# Audio_Alarm_Monitoring_Pi_Hat.net
KiCad netlist of a schematic drawn in EAGLE
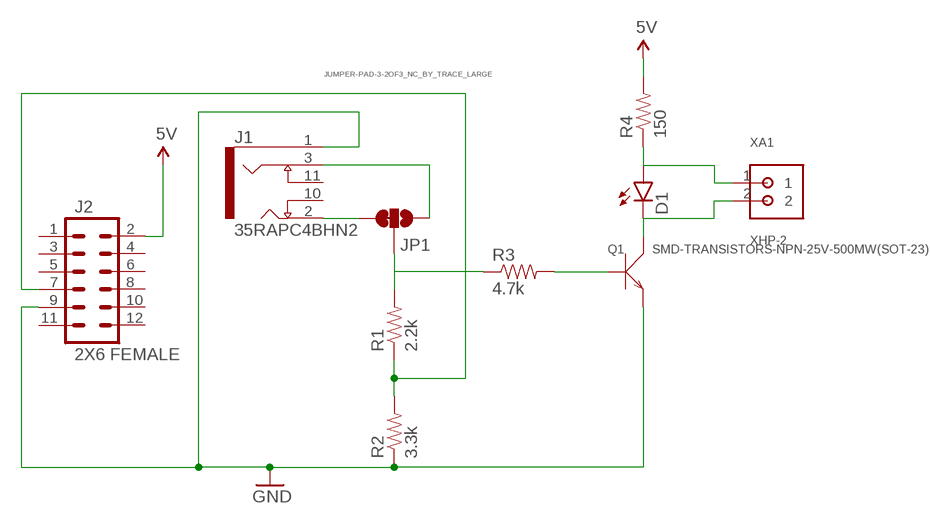
[diagram p0: schematic, sheet 1]

(export (version "E")
  (design (tool "Eeschema 10.0.6"))
  (components
    (comp (ref "D1")
      (value "LED1206")
      (footprint "eagle-import:LED-1206")
      (libsource (lib "eagle-import") (part "LED1206"))
    )
    (comp (ref "J1")
      (value "35RAPC4BHN2")
      (footprint "eagle-import:SWITCHCRAFT_35RAPC4BHN2")
      (fields (field (name "MF") "Switchcraft"))
      (libsource (lib "eagle-import") (part "35RAPC4BHN2"))
    )
    (comp (ref "J2")
      (value "2X6 FEMALE")
      (footprint "eagle-import:2X6")
      (libsource (lib "eagle-import") (part "M06X2PTH_FEMALE"))
    )
    (comp (ref "JP1")
      (value "JUMPER-PAD-3-2OF3_NC_BY_TRACE_LARGE")
      (footprint "eagle-import:PAD-JUMPER-3-2OF3_NC_BY_TRACE_YES_SILK_LARGE")
      (libsource (lib "eagle-import") (part "JUMPER-PAD-3-2OF3_NC_BY_TRACE_LARGE"))
    )
    (comp (ref "Q1")
      (value "SMD-TRANSISTORS-NPN-25V-500MW(SOT-23)")
      (footprint "eagle-import:SOT-23")
      (fields (field (name "MF") "Recom Power") (field (name "MP") "S8050"))
      (libsource (lib "eagle-import") (part "SMD-TRANSISTORS-NPN-25V-500MW(SOT-23)"))
    )
    (comp (ref "R1")
      (value "2.2k")
      (footprint "eagle-import:1206")
      (libsource (lib "eagle-import") (part "RESISTOR1206"))
    )
    (comp (ref "R2")
      (value "3.3k")
      (footprint "eagle-import:1206")
      (libsource (lib "eagle-import") (part "RESISTOR1206"))
    )
    (comp (ref "R3")
      (value "4.7k")
      (footprint "eagle-import:1206")
      (libsource (lib "eagle-import") (part "RESISTOR1206"))
    )
    (comp (ref "R4")
      (value "150")
      (footprint "eagle-import:1206")
      (libsource (lib "eagle-import") (part "RESISTOR1206"))
    )
    (comp (ref "XA1")
      (value "XHP-2")
      (footprint "eagle-import:JST_XHP-2")
      (fields (field (name "MF") "JST Sales"))
      (libsource (lib "eagle-import") (part "XHP-2"))
    )
  )
  (nets
    (net (code "1") (name "5V") (class "Default")
      (node (ref "J2") (pin "2") (pinfunction "2_2") (pintype "passive"))
      (node (ref "R4") (pin "2") (pinfunction "2_2") (pintype "passive"))
    )
    (net (code "2") (name "GND") (class "Default")
      (node (ref "J1") (pin "1") (pinfunction "1_1") (pintype "passive"))
      (node (ref "J2") (pin "9") (pinfunction "9_9") (pintype "passive"))
      (node (ref "Q1") (pin "2") (pinfunction "E_2") (pintype "passive"))
      (node (ref "R2") (pin "1") (pinfunction "1_1") (pintype "passive"))
    )
    (net (code "3") (name "Net-(D1-PadA)") (class "Default")
      (node (ref "D1") (pin "A") (pinfunction "A_A") (pintype "passive"))
      (node (ref "R4") (pin "1") (pinfunction "1_1") (pintype "passive"))
      (node (ref "XA1") (pin "1") (pinfunction "1_1") (pintype "passive"))
    )
    (net (code "4") (name "Net-(J1-Pad2)") (class "Default")
      (node (ref "J1") (pin "2") (pinfunction "2_2") (pintype "passive"))
      (node (ref "JP1") (pin "3") (pinfunction "3_3") (pintype "passive"))
    )
    (net (code "5") (name "Net-(J1-Pad3)") (class "Default")
      (node (ref "J1") (pin "3") (pinfunction "3_3") (pintype "passive"))
      (node (ref "JP1") (pin "1") (pinfunction "1_1") (pintype "passive"))
    )
    (net (code "6") (name "Net-(J2-Pad7)") (class "Default")
      (node (ref "J2") (pin "7") (pinfunction "7_7") (pintype "passive"))
      (node (ref "R1") (pin "1") (pinfunction "1_1") (pintype "passive"))
      (node (ref "R2") (pin "2") (pinfunction "2_2") (pintype "passive"))
    )
    (net (code "7") (name "Net-(JP1-Pad2)") (class "Default")
      (node (ref "JP1") (pin "2") (pinfunction "2_2") (pintype "passive"))
      (node (ref "R1") (pin "2") (pinfunction "2_2") (pintype "passive"))
      (node (ref "R3") (pin "1") (pinfunction "1_1") (pintype "passive"))
    )
    (net (code "8") (name "Net-(Q1-B)") (class "Default")
      (node (ref "Q1") (pin "1") (pinfunction "B_1") (pintype "passive"))
      (node (ref "R3") (pin "2") (pinfunction "2_2") (pintype "passive"))
    )
    (net (code "9") (name "Net-(Q1-C)") (class "Default")
      (node (ref "D1") (pin "C") (pinfunction "C_C") (pintype "passive"))
      (node (ref "Q1") (pin "3") (pinfunction "C_3") (pintype "passive"))
      (node (ref "XA1") (pin "2") (pinfunction "2_2") (pintype "passive"))
    )
    (net (code "10") (name "unconnected-(J1-Pad10)") (class "Default")
      (node (ref "J1") (pin "10") (pinfunction "10_10") (pintype "passive"))
    )
    (net (code "11") (name "unconnected-(J1-Pad11)") (class "Default")
      (node (ref "J1") (pin "11") (pinfunction "11_11") (pintype "passive"))
    )
    (net (code "12") (name "unconnected-(J2-Pad1)") (class "Default")
      (node (ref "J2") (pin "1") (pinfunction "1_1") (pintype "passive"))
    )
    (net (code "13") (name "unconnected-(J2-Pad3)") (class "Default")
      (node (ref "J2") (pin "3") (pinfunction "3_3") (pintype "passive"))
    )
    (net (code "14") (name "unconnected-(J2-Pad4)") (class "Default")
      (node (ref "J2") (pin "4") (pinfunction "4_4") (pintype "passive"))
    )
    (net (code "15") (name "unconnected-(J2-Pad5)") (class "Default")
      (node (ref "J2") (pin "5") (pinfunction "5_5") (pintype "passive"))
    )
    (net (code "16") (name "unconnected-(J2-Pad6)") (class "Default")
      (node (ref "J2") (pin "6") (pinfunction "6_6") (pintype "passive"))
    )
    (net (code "17") (name "unconnected-(J2-Pad8)") (class "Default")
      (node (ref "J2") (pin "8") (pinfunction "8_8") (pintype "passive"))
    )
    (net (code "18") (name "unconnected-(J2-Pad10)") (class "Default")
      (node (ref "J2") (pin "10") (pinfunction "10_10") (pintype "passive"))
    )
    (net (code "19") (name "unconnected-(J2-Pad11)") (class "Default")
      (node (ref "J2") (pin "11") (pinfunction "11_11") (pintype "passive"))
    )
    (net (code "20") (name "unconnected-(J2-Pad12)") (class "Default")
      (node (ref "J2") (pin "12") (pinfunction "12_12") (pintype "passive"))
    )
  )
)
